# encoder_board.net
KiCad netlist of a schematic drawn in EAGLE
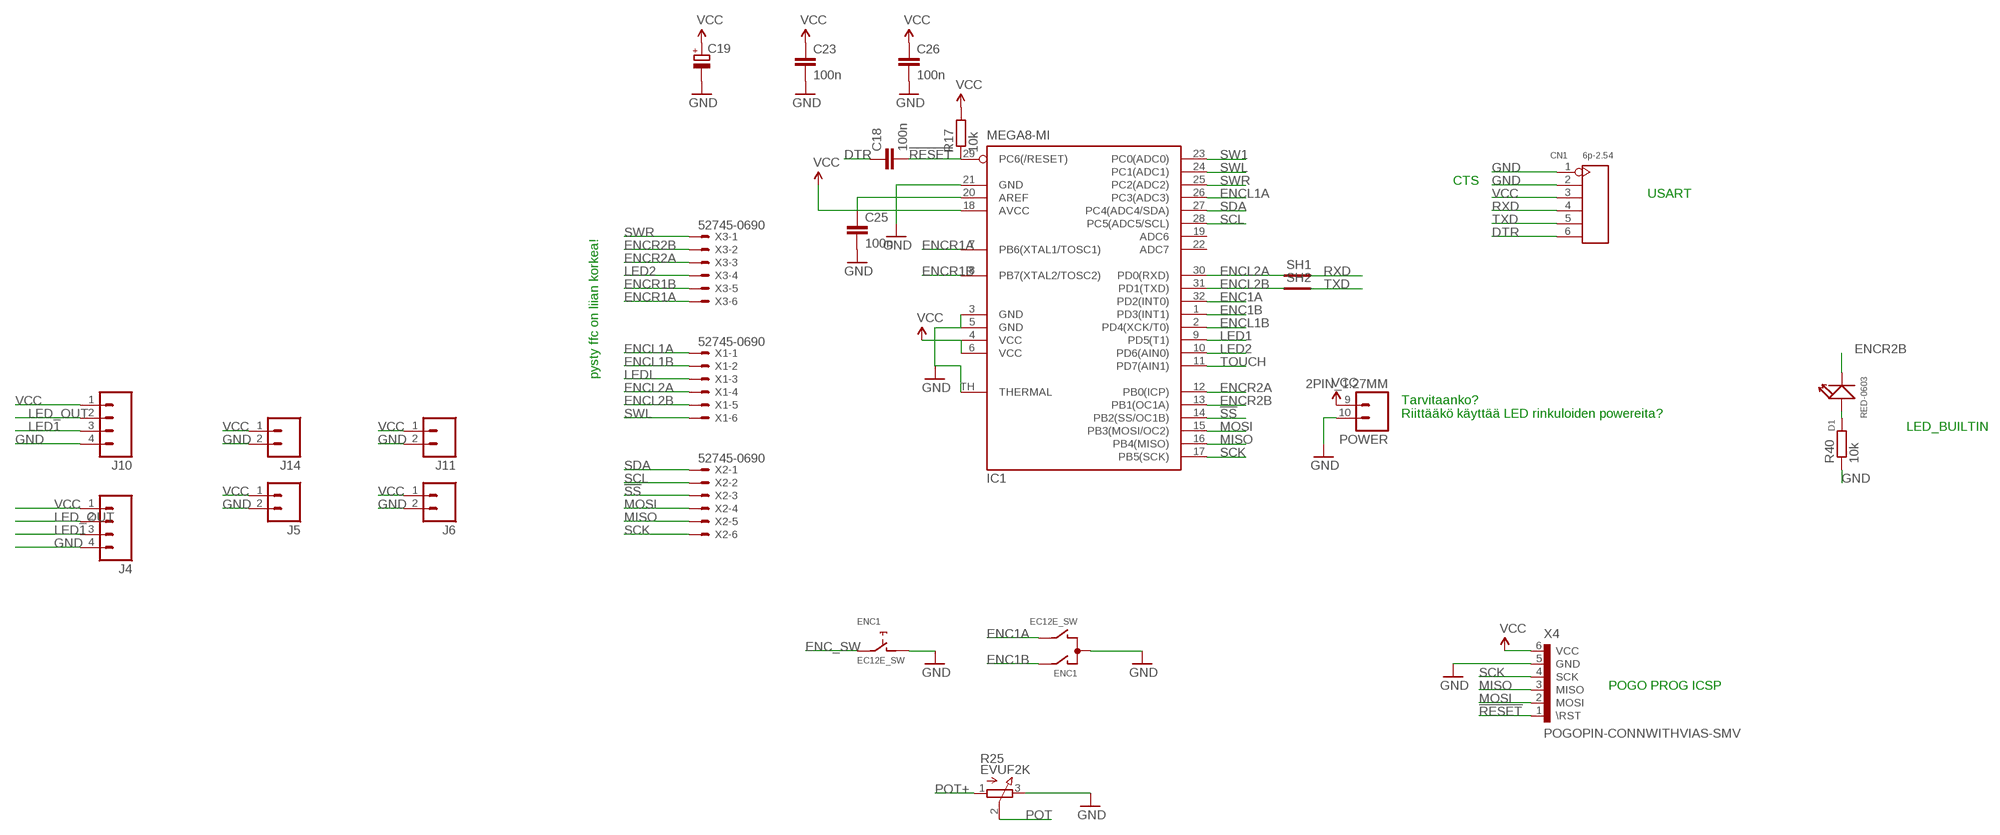
[diagram p0: schematic, sheet 1]
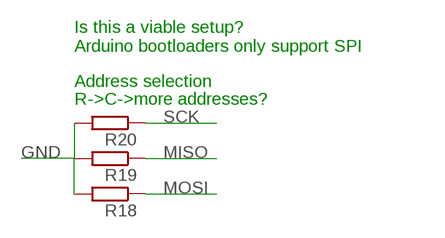
[diagram p1: schematic, sheet 2]
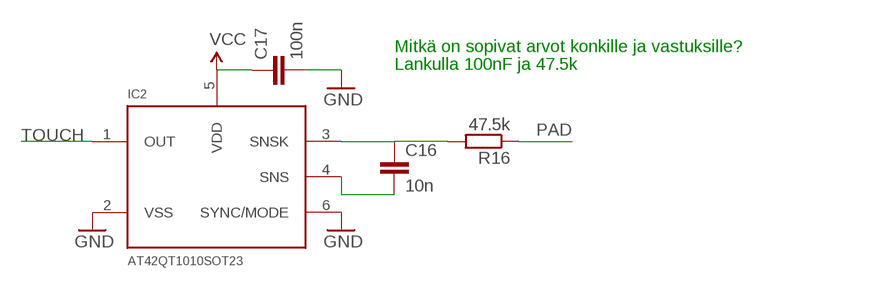
[diagram p2: schematic, sheet 3]
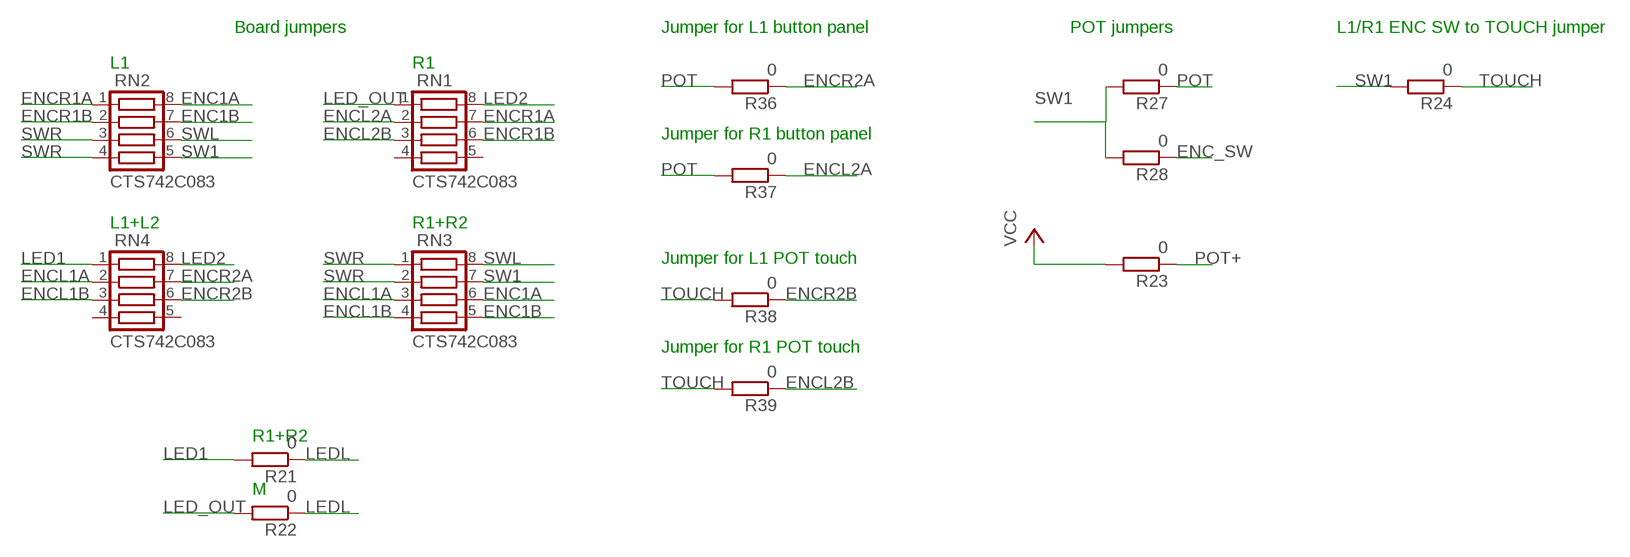
[diagram p3: schematic, sheet 4]

(export (version "E")
  (design (tool "Eeschema 10.0.6"))
  (components
    (comp (ref "C18")
      (value "100n")
      (footprint "eagle-import:0603-CAP")
      (libsource (lib "eagle-import") (part "CAP0603-CAP"))
    )
    (comp (ref "C19")
      (value "CPOL-EUC")
      (footprint "eagle-import:PANASONIC_C")
      (libsource (lib "eagle-import") (part "CPOL-EUC"))
    )
    (comp (ref "C23")
      (value "100n")
      (footprint "eagle-import:0603-CAP")
      (libsource (lib "eagle-import") (part "CAP0603-CAP"))
    )
    (comp (ref "C25")
      (value "100n")
      (footprint "eagle-import:0603-CAP")
      (libsource (lib "eagle-import") (part "CAP0603-CAP"))
    )
    (comp (ref "C26")
      (value "100n")
      (footprint "eagle-import:0603-CAP")
      (libsource (lib "eagle-import") (part "CAP0603-CAP"))
    )
    (comp (ref "CN1")
      (value "6p-2.54")
      (footprint "eagle-import:H6-2.54")
      (fields (field (name "MPN") "F185-1106A1BSYC1"))
      (libsource (lib "eagle-import") (part "DIP-BLACK-FEMALE-HEADER-VERT(6P-2.54)"))
    )
    (comp (ref "D1")
      (value "RED-0603")
      (footprint "eagle-import:LED-0603")
      (fields (field (name "MPN") "19-217-R6C-AL1M2VY-3T"))
      (libsource (lib "eagle-import") (part "LED-SMD-RED-DIFFUSED(0603)"))
    )
    (comp (ref "ENC1")
      (value "EC12E_SW")
      (footprint "eagle-import:ALPS_EC12E_SW")
      (fields (field (name "MPN") "EC12E2424407"))
      (libsource (lib "eagle-import") (part "EC12E_SW"))
    )
    (comp (ref "IC1")
      (value "MEGA8-MI")
      (footprint "eagle-import:MLF32-TH")
      (fields (field (name "MPN") "ATMEGA88PA-MU"))
      (libsource (lib "eagle-import") (part "MEGA8-MI"))
    )
    (comp (ref "J4")
      (value "M04NO_SILK_ALL_ROUND")
      (footprint "eagle-import:1X04_NO_SILK_ALL_ROUND")
      (libsource (lib "eagle-import") (part "M04NO_SILK_ALL_ROUND"))
    )
    (comp (ref "J5")
      (value "M021X02_NO_SILK")
      (footprint "eagle-import:1X02_NO_SILK")
      (libsource (lib "eagle-import") (part "M021X02_NO_SILK"))
    )
    (comp (ref "J6")
      (value "M021X02_NO_SILK")
      (footprint "eagle-import:1X02_NO_SILK")
      (libsource (lib "eagle-import") (part "M021X02_NO_SILK"))
    )
    (comp (ref "J10")
      (value "M04NO_SILK_ALL_ROUND")
      (footprint "eagle-import:1X04_NO_SILK_ALL_ROUND")
      (libsource (lib "eagle-import") (part "M04NO_SILK_ALL_ROUND"))
    )
    (comp (ref "J11")
      (value "M021X02_NO_SILK")
      (footprint "eagle-import:1X02_NO_SILK")
      (libsource (lib "eagle-import") (part "M021X02_NO_SILK"))
    )
    (comp (ref "J14")
      (value "M021X02_NO_SILK")
      (footprint "eagle-import:1X02_NO_SILK")
      (libsource (lib "eagle-import") (part "M021X02_NO_SILK"))
    )
    (comp (ref "POWER")
      (value "2PIN_1.27MM")
      (footprint "eagle-import:1X02_1.27MM_NO_SILK")
      (libsource (lib "eagle-import") (part "2PIN_1.27MM"))
    )
    (comp (ref "R17")
      (value "10k")
      (footprint "eagle-import:R0603")
      (libsource (lib "eagle-import") (part "R-EU_R0603"))
    )
    (comp (ref "R25")
      (value "EVUF2K")
      (footprint "eagle-import:EVUFXK")
      (libsource (lib "eagle-import") (part "EVUF2K"))
    )
    (comp (ref "R40")
      (value "10k")
      (footprint "eagle-import:R0603")
      (libsource (lib "eagle-import") (part "R-EU_R0603"))
    )
    (comp (ref "SH1")
      (value "SHORT")
      (footprint "eagle-import:SHORT_TOP_8MIL")
      (libsource (lib "eagle-import") (part "SHORT"))
    )
    (comp (ref "SH2")
      (value "SHORT")
      (footprint "eagle-import:SHORT_TOP_8MIL")
      (libsource (lib "eagle-import") (part "SHORT"))
    )
    (comp (ref "X1")
      (value "52745-0690")
      (footprint "eagle-import:52745-0690")
      (fields (field (name "MF") "MOLEX"))
      (libsource (lib "eagle-import") (part "52745-0690"))
    )
    (comp (ref "X2")
      (value "52745-0690")
      (footprint "eagle-import:52745-0690")
      (fields (field (name "MF") "MOLEX"))
      (libsource (lib "eagle-import") (part "52745-0690"))
    )
    (comp (ref "X3")
      (value "52745-0690")
      (footprint "eagle-import:52745-0690")
      (fields (field (name "MF") "MOLEX"))
      (libsource (lib "eagle-import") (part "52745-0690"))
    )
    (comp (ref "X4")
      (value "POGOPIN-CONNWITHVIAS-SMV")
      (footprint "eagle-import:POGOPROG-CONN-OH-SMALLERVIAS")
      (libsource (lib "eagle-import") (part "POGOPIN-CONNWITHVIAS-SMV"))
    )
    (comp (ref "R18")
      (value "R-EU_R0603")
      (footprint "eagle-import:R0603")
      (libsource (lib "eagle-import") (part "R-EU_R0603"))
    )
    (comp (ref "R19")
      (value "R-EU_R0603")
      (footprint "eagle-import:R0603")
      (libsource (lib "eagle-import") (part "R-EU_R0603"))
    )
    (comp (ref "R20")
      (value "R-EU_R0603")
      (footprint "eagle-import:R0603")
      (libsource (lib "eagle-import") (part "R-EU_R0603"))
    )
    (comp (ref "C16")
      (value "10n")
      (footprint "eagle-import:0603-CAP")
      (libsource (lib "eagle-import") (part "CAP0603-CAP"))
    )
    (comp (ref "C17")
      (value "100n")
      (footprint "eagle-import:0603-CAP")
      (libsource (lib "eagle-import") (part "CAP0603-CAP"))
    )
    (comp (ref "IC2")
      (value "AT42QT1010SOT23")
      (footprint "eagle-import:SOT23-6")
      (libsource (lib "eagle-import") (part "AT42QT1010SOT23"))
    )
    (comp (ref "R16")
      (value "47.5k")
      (footprint "eagle-import:R0603")
      (libsource (lib "eagle-import") (part "R-EU_R0603"))
    )
    (comp (ref "R21")
      (value "0")
      (footprint "eagle-import:R0603")
      (libsource (lib "eagle-import") (part "R-EU_R0603"))
    )
    (comp (ref "R22")
      (value "0")
      (footprint "eagle-import:R0603")
      (fields (field (name "SPICEPREFIX") "R"))
      (libsource (lib "eagle-import") (part "R-EU_R0603"))
    )
    (comp (ref "R23")
      (value "0")
      (footprint "eagle-import:R0603")
      (fields (field (name "SPICEPREFIX") "R"))
      (libsource (lib "eagle-import") (part "R-EU_R0603"))
    )
    (comp (ref "R24")
      (value "0")
      (footprint "eagle-import:R0603")
      (fields (field (name "SPICEPREFIX") "R"))
      (libsource (lib "eagle-import") (part "R-EU_R0603"))
    )
    (comp (ref "R27")
      (value "0")
      (footprint "eagle-import:R0603")
      (fields (field (name "SPICEPREFIX") "R"))
      (libsource (lib "eagle-import") (part "R-EU_R0603"))
    )
    (comp (ref "R28")
      (value "0")
      (footprint "eagle-import:R0603")
      (fields (field (name "SPICEPREFIX") "R"))
      (libsource (lib "eagle-import") (part "R-EU_R0603"))
    )
    (comp (ref "R36")
      (value "0")
      (footprint "eagle-import:R0603")
      (fields (field (name "SPICEPREFIX") "R"))
      (libsource (lib "eagle-import") (part "R-EU_R0603"))
    )
    (comp (ref "R37")
      (value "0")
      (footprint "eagle-import:R0603")
      (fields (field (name "SPICEPREFIX") "R"))
      (libsource (lib "eagle-import") (part "R-EU_R0603"))
    )
    (comp (ref "R38")
      (value "0")
      (footprint "eagle-import:R0603")
      (fields (field (name "SPICEPREFIX") "R"))
      (libsource (lib "eagle-import") (part "R-EU_R0603"))
    )
    (comp (ref "R39")
      (value "0")
      (footprint "eagle-import:R0603")
      (fields (field (name "SPICEPREFIX") "R"))
      (libsource (lib "eagle-import") (part "R-EU_R0603"))
    )
    (comp (ref "RN1")
      (value "CTS742C083")
      (footprint "eagle-import:CTS742C083")
      (libsource (lib "eagle-import") (part "CTS742C083"))
    )
    (comp (ref "RN2")
      (value "CTS742C083")
      (footprint "eagle-import:CTS742C083")
      (libsource (lib "eagle-import") (part "CTS742C083"))
    )
    (comp (ref "RN3")
      (value "CTS742C083")
      (footprint "eagle-import:CTS742C083")
      (libsource (lib "eagle-import") (part "CTS742C083"))
    )
    (comp (ref "RN4")
      (value "CTS742C083")
      (footprint "eagle-import:CTS742C083")
      (libsource (lib "eagle-import") (part "CTS742C083"))
    )
  )
  (nets
    (net (code "1") (name "DTR") (class "Default")
      (node (ref "C18") (pin "1") (pinfunction "1_1") (pintype "passive"))
      (node (ref "CN1") (pin "6") (pinfunction "6_6") (pintype "bidirectional"))
    )
    (net (code "2") (name "ENC1A") (class "Default")
      (node (ref "ENC1") (pin "B") (pinfunction "B_B") (pintype "passive"))
      (node (ref "IC1") (pin "32") (pinfunction "PD2(INT0)_32") (pintype "bidirectional"))
      (node (ref "RN2") (pin "8") (pinfunction "8_8") (pintype "passive"))
      (node (ref "RN3") (pin "6") (pinfunction "6_6") (pintype "passive"))
    )
    (net (code "3") (name "ENC1B") (class "Default")
      (node (ref "ENC1") (pin "A") (pinfunction "A_A") (pintype "passive"))
      (node (ref "IC1") (pin "1") (pinfunction "PD3(INT1)_1") (pintype "bidirectional"))
      (node (ref "RN2") (pin "7") (pinfunction "7_7") (pintype "passive"))
      (node (ref "RN3") (pin "5") (pinfunction "5_5") (pintype "passive"))
    )
    (net (code "4") (name "ENCL1A") (class "Default")
      (node (ref "IC1") (pin "26") (pinfunction "PC3(ADC3)_26") (pintype "bidirectional"))
      (node (ref "RN3") (pin "3") (pinfunction "3_3") (pintype "passive"))
      (node (ref "RN4") (pin "2") (pinfunction "2_2") (pintype "passive"))
      (node (ref "X1") (pin "1") (pinfunction "S_1") (pintype "passive"))
    )
    (net (code "5") (name "ENCL1B") (class "Default")
      (node (ref "IC1") (pin "2") (pinfunction "PD4(XCK/T0)_2") (pintype "bidirectional"))
      (node (ref "RN3") (pin "4") (pinfunction "4_4") (pintype "passive"))
      (node (ref "RN4") (pin "3") (pinfunction "3_3") (pintype "passive"))
      (node (ref "X1") (pin "2") (pinfunction "S_2") (pintype "passive"))
    )
    (net (code "6") (name "ENCL2A") (class "Default")
      (node (ref "IC1") (pin "30") (pinfunction "PD0(RXD)_30") (pintype "bidirectional"))
      (node (ref "R37") (pin "1") (pinfunction "1_1") (pintype "passive"))
      (node (ref "RN1") (pin "2") (pinfunction "2_2") (pintype "passive"))
      (node (ref "SH1") (pin "P$1") (pinfunction "P$1_P$1") (pintype "bidirectional"))
      (node (ref "X1") (pin "4") (pinfunction "S_4") (pintype "passive"))
    )
    (net (code "7") (name "ENCL2B") (class "Default")
      (node (ref "IC1") (pin "31") (pinfunction "PD1(TXD)_31") (pintype "bidirectional"))
      (node (ref "R39") (pin "1") (pinfunction "1_1") (pintype "passive"))
      (node (ref "RN1") (pin "3") (pinfunction "3_3") (pintype "passive"))
      (node (ref "SH2") (pin "P$1") (pinfunction "P$1_P$1") (pintype "bidirectional"))
      (node (ref "X1") (pin "5") (pinfunction "S_5") (pintype "passive"))
    )
    (net (code "8") (name "ENCR1A") (class "Default")
      (node (ref "IC1") (pin "7") (pinfunction "PB6(XTAL1/TOSC1)_7") (pintype "bidirectional"))
      (node (ref "RN1") (pin "7") (pinfunction "7_7") (pintype "passive"))
      (node (ref "RN2") (pin "1") (pinfunction "1_1") (pintype "passive"))
      (node (ref "X3") (pin "6") (pinfunction "S_6") (pintype "passive"))
    )
    (net (code "9") (name "ENCR1B") (class "Default")
      (node (ref "IC1") (pin "8") (pinfunction "PB7(XTAL2/TOSC2)_8") (pintype "bidirectional"))
      (node (ref "RN1") (pin "6") (pinfunction "6_6") (pintype "passive"))
      (node (ref "RN2") (pin "2") (pinfunction "2_2") (pintype "passive"))
      (node (ref "X3") (pin "5") (pinfunction "S_5") (pintype "passive"))
    )
    (net (code "10") (name "ENCR2A") (class "Default")
      (node (ref "IC1") (pin "12") (pinfunction "PB0(ICP)_12") (pintype "bidirectional"))
      (node (ref "R36") (pin "1") (pinfunction "1_1") (pintype "passive"))
      (node (ref "RN4") (pin "7") (pinfunction "7_7") (pintype "passive"))
      (node (ref "X3") (pin "3") (pinfunction "S_3") (pintype "passive"))
    )
    (net (code "11") (name "ENCR2B") (class "Default")
      (node (ref "D1") (pin "-") (pinfunction "-_-") (pintype "passive"))
      (node (ref "IC1") (pin "13") (pinfunction "PB1(OC1A)_13") (pintype "bidirectional"))
      (node (ref "R38") (pin "1") (pinfunction "1_1") (pintype "passive"))
      (node (ref "RN4") (pin "6") (pinfunction "6_6") (pintype "passive"))
      (node (ref "X3") (pin "2") (pinfunction "S_2") (pintype "passive"))
    )
    (net (code "12") (name "ENC_SW") (class "Default")
      (node (ref "ENC1") (pin "E") (pinfunction "2_E") (pintype "passive"))
      (node (ref "R28") (pin "1") (pinfunction "1_1") (pintype "passive"))
    )
    (net (code "13") (name "GND") (class "Default")
      (node (ref "C17") (pin "2") (pinfunction "2_2") (pintype "passive"))
      (node (ref "C19") (pin "-") (pinfunction "-_-") (pintype "passive"))
      (node (ref "C23") (pin "2") (pinfunction "2_2") (pintype "passive"))
      (node (ref "C25") (pin "2") (pinfunction "2_2") (pintype "passive"))
      (node (ref "C26") (pin "2") (pinfunction "2_2") (pintype "passive"))
      (node (ref "CN1") (pin "1") (pinfunction "1_1") (pintype "bidirectional"))
      (node (ref "CN1") (pin "2") (pinfunction "2_2") (pintype "bidirectional"))
      (node (ref "ENC1") (pin "C") (pinfunction "C_C") (pintype "passive"))
      (node (ref "ENC1") (pin "D") (pinfunction "1_D") (pintype "passive"))
      (node (ref "IC1") (pin "21") (pinfunction "GND_21") (pintype "power_in"))
      (node (ref "IC1") (pin "3") (pinfunction "GND_3") (pintype "power_in"))
      (node (ref "IC1") (pin "5") (pinfunction "GND_5") (pintype "power_in"))
      (node (ref "IC1") (pin "TH") (pinfunction "THERMAL_TH") (pintype "passive"))
      (node (ref "IC2") (pin "2") (pinfunction "VSS_2") (pintype "bidirectional"))
      (node (ref "IC2") (pin "6") (pinfunction "SYNC/MODE_6") (pintype "bidirectional"))
      (node (ref "J10") (pin "4") (pinfunction "4_4") (pintype "passive"))
      (node (ref "J11") (pin "2") (pinfunction "2_2") (pintype "passive"))
      (node (ref "J14") (pin "2") (pinfunction "2_2") (pintype "passive"))
      (node (ref "J4") (pin "4") (pinfunction "4_4") (pintype "passive"))
      (node (ref "J5") (pin "2") (pinfunction "2_2") (pintype "passive"))
      (node (ref "J6") (pin "2") (pinfunction "2_2") (pintype "passive"))
      (node (ref "POWER") (pin "10") (pinfunction "2_10") (pintype "passive"))
      (node (ref "R18") (pin "2") (pinfunction "2_2") (pintype "passive"))
      (node (ref "R19") (pin "2") (pinfunction "2_2") (pintype "passive"))
      (node (ref "R20") (pin "2") (pinfunction "2_2") (pintype "passive"))
      (node (ref "R25") (pin "3") (pinfunction "E_3") (pintype "passive"))
      (node (ref "R40") (pin "1") (pinfunction "1_1") (pintype "passive"))
      (node (ref "X4") (pin "5") (pinfunction "GND_5") (pintype "bidirectional"))
    )
    (net (code "14") (name "LED1") (class "Default")
      (node (ref "IC1") (pin "9") (pinfunction "PD5(T1)_9") (pintype "bidirectional"))
      (node (ref "J10") (pin "3") (pinfunction "3_3") (pintype "passive"))
      (node (ref "J4") (pin "3") (pinfunction "3_3") (pintype "passive"))
      (node (ref "R21") (pin "2") (pinfunction "2_2") (pintype "passive"))
      (node (ref "RN4") (pin "1") (pinfunction "1_1") (pintype "passive"))
    )
    (net (code "15") (name "LED2") (class "Default")
      (node (ref "IC1") (pin "10") (pinfunction "PD6(AIN0)_10") (pintype "bidirectional"))
      (node (ref "RN1") (pin "8") (pinfunction "8_8") (pintype "passive"))
      (node (ref "RN4") (pin "8") (pinfunction "8_8") (pintype "passive"))
      (node (ref "X3") (pin "4") (pinfunction "S_4") (pintype "passive"))
    )
    (net (code "16") (name "LEDL") (class "Default")
      (node (ref "R21") (pin "1") (pinfunction "1_1") (pintype "passive"))
      (node (ref "R22") (pin "1") (pinfunction "1_1") (pintype "passive"))
      (node (ref "X1") (pin "3") (pinfunction "S_3") (pintype "passive"))
    )
    (net (code "17") (name "LED_OUT") (class "Default")
      (node (ref "J10") (pin "2") (pinfunction "2_2") (pintype "passive"))
      (node (ref "J4") (pin "2") (pinfunction "2_2") (pintype "passive"))
      (node (ref "R22") (pin "2") (pinfunction "2_2") (pintype "passive"))
      (node (ref "RN1") (pin "1") (pinfunction "1_1") (pintype "passive"))
    )
    (net (code "18") (name "MISO") (class "Default")
      (node (ref "IC1") (pin "16") (pinfunction "PB4(MISO)_16") (pintype "bidirectional"))
      (node (ref "R19") (pin "1") (pinfunction "1_1") (pintype "passive"))
      (node (ref "X2") (pin "5") (pinfunction "S_5") (pintype "passive"))
      (node (ref "X4") (pin "3") (pinfunction "MISO_3") (pintype "bidirectional"))
    )
    (net (code "19") (name "MOSI") (class "Default")
      (node (ref "IC1") (pin "15") (pinfunction "PB3(MOSI/OC2)_15") (pintype "bidirectional"))
      (node (ref "R18") (pin "1") (pinfunction "1_1") (pintype "passive"))
      (node (ref "X2") (pin "4") (pinfunction "S_4") (pintype "passive"))
      (node (ref "X4") (pin "2") (pinfunction "MOSI_2") (pintype "bidirectional"))
    )
    (net (code "20") (name "Net-(D1-Pad+)") (class "Default")
      (node (ref "D1") (pin "+") (pinfunction "+_+") (pintype "passive"))
      (node (ref "R40") (pin "2") (pinfunction "2_2") (pintype "passive"))
    )
    (net (code "21") (name "Net-(IC1-AREF)") (class "Default")
      (node (ref "C25") (pin "1") (pinfunction "1_1") (pintype "passive"))
      (node (ref "IC1") (pin "20") (pinfunction "AREF_20") (pintype "passive"))
    )
    (net (code "22") (name "Net-(IC2-SNS)") (class "Default")
      (node (ref "C16") (pin "2") (pinfunction "2_2") (pintype "passive"))
      (node (ref "IC2") (pin "4") (pinfunction "SNS_4") (pintype "bidirectional"))
    )
    (net (code "23") (name "Net-(IC2-SNSK)") (class "Default")
      (node (ref "C16") (pin "1") (pinfunction "1_1") (pintype "passive"))
      (node (ref "IC2") (pin "3") (pinfunction "SNSK_3") (pintype "bidirectional"))
      (node (ref "R16") (pin "2") (pinfunction "2_2") (pintype "passive"))
    )
    (net (code "24") (name "PAD") (class "Default")
      (node (ref "R16") (pin "1") (pinfunction "1_1") (pintype "passive"))
    )
    (net (code "25") (name "POT") (class "Default")
      (node (ref "R25") (pin "2") (pinfunction "S_2") (pintype "passive"))
      (node (ref "R27") (pin "1") (pinfunction "1_1") (pintype "passive"))
      (node (ref "R36") (pin "2") (pinfunction "2_2") (pintype "passive"))
      (node (ref "R37") (pin "2") (pinfunction "2_2") (pintype "passive"))
    )
    (net (code "26") (name "POT+") (class "Default")
      (node (ref "R23") (pin "1") (pinfunction "1_1") (pintype "passive"))
      (node (ref "R25") (pin "1") (pinfunction "A_1") (pintype "passive"))
    )
    (net (code "27") (name "RXD") (class "Default")
      (node (ref "CN1") (pin "4") (pinfunction "4_4") (pintype "bidirectional"))
      (node (ref "SH1") (pin "P$2") (pinfunction "P$2_P$2") (pintype "bidirectional"))
    )
    (net (code "28") (name "SCK") (class "Default")
      (node (ref "IC1") (pin "17") (pinfunction "PB5(SCK)_17") (pintype "bidirectional"))
      (node (ref "R20") (pin "1") (pinfunction "1_1") (pintype "passive"))
      (node (ref "X2") (pin "6") (pinfunction "S_6") (pintype "passive"))
      (node (ref "X4") (pin "4") (pinfunction "SCK_4") (pintype "bidirectional"))
    )
    (net (code "29") (name "SCL") (class "Default")
      (node (ref "IC1") (pin "28") (pinfunction "PC5(ADC5/SCL)_28") (pintype "bidirectional"))
      (node (ref "X2") (pin "2") (pinfunction "S_2") (pintype "passive"))
    )
    (net (code "30") (name "SDA") (class "Default")
      (node (ref "IC1") (pin "27") (pinfunction "PC4(ADC4/SDA)_27") (pintype "bidirectional"))
      (node (ref "X2") (pin "1") (pinfunction "S_1") (pintype "passive"))
    )
    (net (code "31") (name "SW1") (class "Default")
      (node (ref "IC1") (pin "23") (pinfunction "PC0(ADC0)_23") (pintype "bidirectional"))
      (node (ref "R24") (pin "2") (pinfunction "2_2") (pintype "passive"))
      (node (ref "R27") (pin "2") (pinfunction "2_2") (pintype "passive"))
      (node (ref "R28") (pin "2") (pinfunction "2_2") (pintype "passive"))
      (node (ref "RN2") (pin "5") (pinfunction "5_5") (pintype "passive"))
      (node (ref "RN3") (pin "7") (pinfunction "7_7") (pintype "passive"))
    )
    (net (code "32") (name "SWL") (class "Default")
      (node (ref "IC1") (pin "24") (pinfunction "PC1(ADC1)_24") (pintype "bidirectional"))
      (node (ref "RN2") (pin "6") (pinfunction "6_6") (pintype "passive"))
      (node (ref "RN3") (pin "8") (pinfunction "8_8") (pintype "passive"))
      (node (ref "X1") (pin "6") (pinfunction "S_6") (pintype "passive"))
    )
    (net (code "33") (name "SWR") (class "Default")
      (node (ref "IC1") (pin "25") (pinfunction "PC2(ADC2)_25") (pintype "bidirectional"))
      (node (ref "RN2") (pin "3") (pinfunction "3_3") (pintype "passive"))
      (node (ref "RN2") (pin "4") (pinfunction "4_4") (pintype "passive"))
      (node (ref "RN3") (pin "1") (pinfunction "1_1") (pintype "passive"))
      (node (ref "RN3") (pin "2") (pinfunction "2_2") (pintype "passive"))
      (node (ref "X3") (pin "1") (pinfunction "S_1") (pintype "passive"))
    )
    (net (code "34") (name "TOUCH") (class "Default")
      (node (ref "IC1") (pin "11") (pinfunction "PD7(AIN1)_11") (pintype "bidirectional"))
      (node (ref "IC2") (pin "1") (pinfunction "OUT_1") (pintype "bidirectional"))
      (node (ref "R24") (pin "1") (pinfunction "1_1") (pintype "passive"))
      (node (ref "R38") (pin "2") (pinfunction "2_2") (pintype "passive"))
      (node (ref "R39") (pin "2") (pinfunction "2_2") (pintype "passive"))
    )
    (net (code "35") (name "TXD") (class "Default")
      (node (ref "CN1") (pin "5") (pinfunction "5_5") (pintype "bidirectional"))
      (node (ref "SH2") (pin "P$2") (pinfunction "P$2_P$2") (pintype "bidirectional"))
    )
    (net (code "36") (name "VCC") (class "Default")
      (node (ref "C17") (pin "1") (pinfunction "1_1") (pintype "passive"))
      (node (ref "C19") (pin "+") (pinfunction "+_+") (pintype "passive"))
      (node (ref "C23") (pin "1") (pinfunction "1_1") (pintype "passive"))
      (node (ref "C26") (pin "1") (pinfunction "1_1") (pintype "passive"))
      (node (ref "CN1") (pin "3") (pinfunction "3_3") (pintype "bidirectional"))
      (node (ref "IC1") (pin "18") (pinfunction "AVCC_18") (pintype "power_in"))
      (node (ref "IC1") (pin "4") (pinfunction "VCC_4") (pintype "power_in"))
      (node (ref "IC1") (pin "6") (pinfunction "VCC_6") (pintype "power_in"))
      (node (ref "IC2") (pin "5") (pinfunction "VDD_5") (pintype "bidirectional"))
      (node (ref "J10") (pin "1") (pinfunction "1_1") (pintype "passive"))
      (node (ref "J11") (pin "1") (pinfunction "1_1") (pintype "passive"))
      (node (ref "J14") (pin "1") (pinfunction "1_1") (pintype "passive"))
      (node (ref "J4") (pin "1") (pinfunction "1_1") (pintype "passive"))
      (node (ref "J5") (pin "1") (pinfunction "1_1") (pintype "passive"))
      (node (ref "J6") (pin "1") (pinfunction "1_1") (pintype "passive"))
      (node (ref "POWER") (pin "9") (pinfunction "1_9") (pintype "passive"))
      (node (ref "R17") (pin "2") (pinfunction "2_2") (pintype "passive"))
      (node (ref "R23") (pin "2") (pinfunction "2_2") (pintype "passive"))
      (node (ref "X4") (pin "6") (pinfunction "VCC_6") (pintype "bidirectional"))
    )
    (net (code "37") (name "unconnected-(IC1-ADC6-Pad19)") (class "Default")
      (node (ref "IC1") (pin "19") (pinfunction "ADC6_19") (pintype "bidirectional"))
    )
    (net (code "38") (name "unconnected-(IC1-ADC7-Pad22)") (class "Default")
      (node (ref "IC1") (pin "22") (pinfunction "ADC7_22") (pintype "bidirectional"))
    )
    (net (code "39") (name "unconnected-(RN1-Pad4)") (class "Default")
      (node (ref "RN1") (pin "4") (pinfunction "4_4") (pintype "passive"))
    )
    (net (code "40") (name "unconnected-(RN1-Pad5)") (class "Default")
      (node (ref "RN1") (pin "5") (pinfunction "5_5") (pintype "passive"))
    )
    (net (code "41") (name "unconnected-(RN4-Pad4)") (class "Default")
      (node (ref "RN4") (pin "4") (pinfunction "4_4") (pintype "passive"))
    )
    (net (code "42") (name "unconnected-(RN4-Pad5)") (class "Default")
      (node (ref "RN4") (pin "5") (pinfunction "5_5") (pintype "passive"))
    )
    (net (code "43") (name "~{RESET}") (class "Default")
      (node (ref "C18") (pin "2") (pinfunction "2_2") (pintype "passive"))
      (node (ref "IC1") (pin "29") (pinfunction "PC6(/RESET)_29") (pintype "bidirectional"))
      (node (ref "R17") (pin "1") (pinfunction "1_1") (pintype "passive"))
      (node (ref "X4") (pin "1") (pinfunction "\\RST_1") (pintype "bidirectional"))
    )
    (net (code "44") (name "~{SS}") (class "Default")
      (node (ref "IC1") (pin "14") (pinfunction "PB2(SS/OC1B)_14") (pintype "bidirectional"))
      (node (ref "X2") (pin "3") (pinfunction "S_3") (pintype "passive"))
    )
  )
)
